# audio3.net
KiCad netlist of a schematic drawn in EAGLE
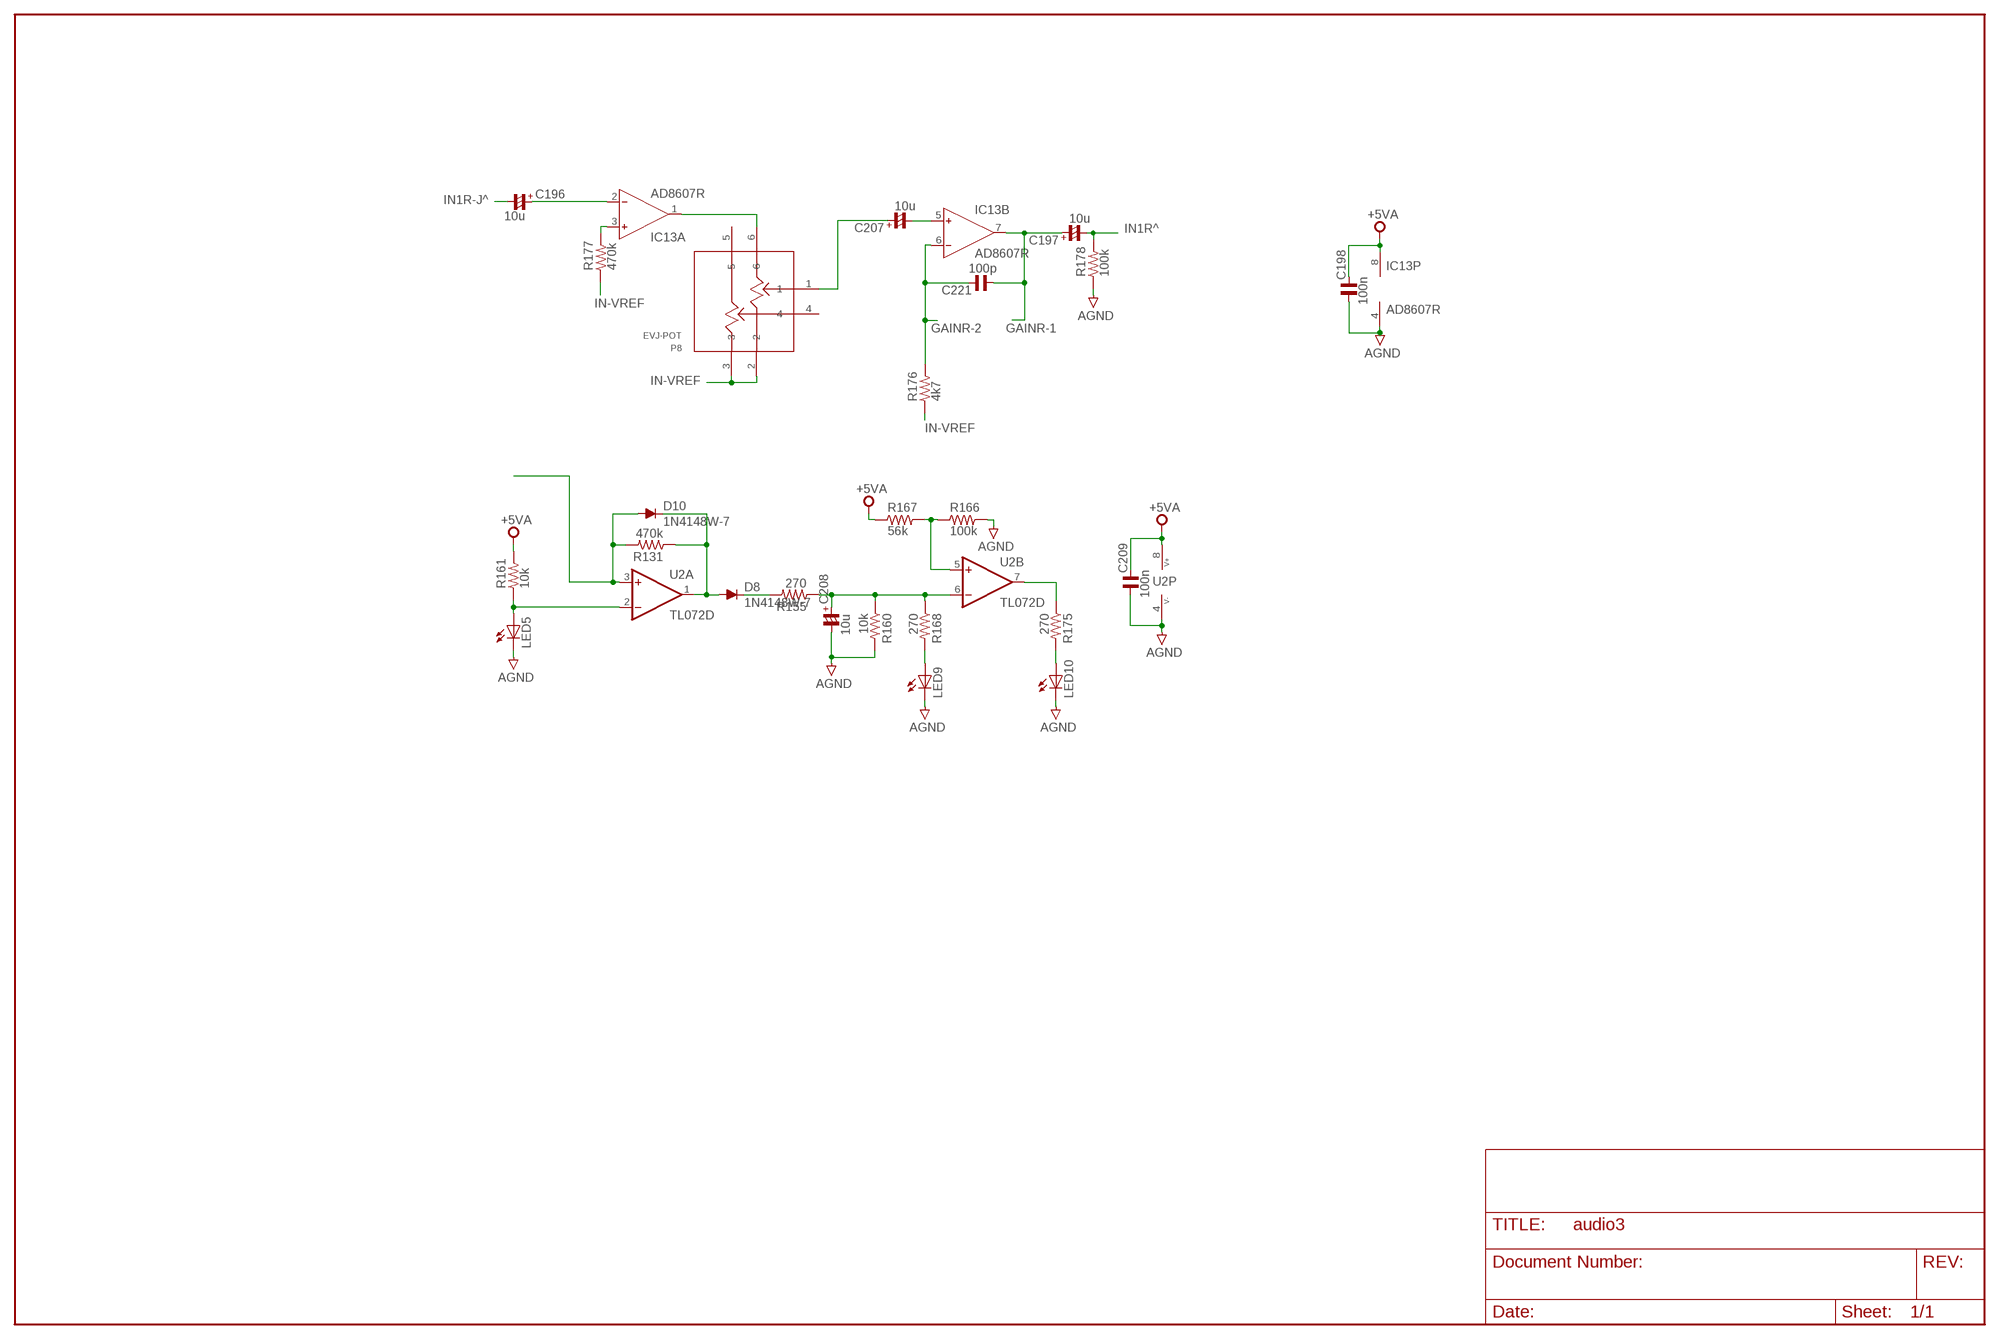
[diagram p0: schematic, sheet 1]

(export (version "E")
  (design (tool "Eeschema 10.0.6"))
  (components
    (comp (ref "C196")
      (value "10u")
      (footprint "eagle-import:C1206_T")
      (libsource (lib "eagle-import") (part "CP_1206/T"))
    )
    (comp (ref "C197")
      (value "10u")
      (footprint "eagle-import:C1206_T")
      (libsource (lib "eagle-import") (part "CP_1206/T"))
    )
    (comp (ref "C198")
      (value "100n")
      (footprint "eagle-import:C0603")
      (libsource (lib "eagle-import") (part "C_0603"))
    )
    (comp (ref "C207")
      (value "10u")
      (footprint "eagle-import:C1206_T")
      (libsource (lib "eagle-import") (part "CP_1206/T"))
    )
    (comp (ref "C208")
      (value "10u")
      (footprint "eagle-import:C1206_T")
      (libsource (lib "eagle-import") (part "CP_1206/T"))
    )
    (comp (ref "C209")
      (value "100n")
      (footprint "eagle-import:C0603")
      (libsource (lib "eagle-import") (part "C_0603"))
    )
    (comp (ref "C221")
      (value "100p")
      (footprint "eagle-import:C0603")
      (libsource (lib "eagle-import") (part "C_0603"))
    )
    (comp (ref "D8")
      (value "1N4148W-7")
      (footprint "eagle-import:SOD123")
      (libsource (lib "eagle-import") (part "1N4148W-7"))
    )
    (comp (ref "D10")
      (value "1N4148W-7")
      (footprint "eagle-import:SOD123")
      (libsource (lib "eagle-import") (part "1N4148W-7"))
    )
    (comp (ref "IC13")
      (value "AD8607R")
      (footprint "eagle-import:SO8")
      (fields (field (name "MPN") "AD8607ARMZ-R2"))
      (libsource (lib "eagle-import") (part "AD8607R"))
    )
    (comp (ref "LED5")
      (value "LEDCHIPLED_0805")
      (footprint "eagle-import:CHIPLED_0805")
      (libsource (lib "eagle-import") (part "LEDCHIPLED_0805"))
    )
    (comp (ref "LED9")
      (value "LEDCHIPLED_0805")
      (footprint "eagle-import:CHIPLED_0805")
      (libsource (lib "eagle-import") (part "LEDCHIPLED_0805"))
    )
    (comp (ref "LED10")
      (value "LEDCHIPLED_0805")
      (footprint "eagle-import:CHIPLED_0805")
      (libsource (lib "eagle-import") (part "LEDCHIPLED_0805"))
    )
    (comp (ref "P8")
      (value "EVJ-POT")
      (footprint "eagle-import:EVJ-POT")
      (libsource (lib "eagle-import") (part "EVJ-POT"))
    )
    (comp (ref "R131")
      (value "470k")
      (footprint "eagle-import:R0603")
      (libsource (lib "eagle-import") (part "R_0603"))
    )
    (comp (ref "R155")
      (value "270")
      (footprint "eagle-import:R0603")
      (libsource (lib "eagle-import") (part "R_0603"))
    )
    (comp (ref "R160")
      (value "10k")
      (footprint "eagle-import:R0603")
      (libsource (lib "eagle-import") (part "R_0603"))
    )
    (comp (ref "R161")
      (value "10k")
      (footprint "eagle-import:R0603")
      (libsource (lib "eagle-import") (part "R_0603"))
    )
    (comp (ref "R166")
      (value "100k")
      (footprint "eagle-import:R0603")
      (libsource (lib "eagle-import") (part "R_0603"))
    )
    (comp (ref "R167")
      (value "56k")
      (footprint "eagle-import:R0603")
      (libsource (lib "eagle-import") (part "R_0603"))
    )
    (comp (ref "R168")
      (value "270")
      (footprint "eagle-import:R0603")
      (libsource (lib "eagle-import") (part "R_0603"))
    )
    (comp (ref "R175")
      (value "270")
      (footprint "eagle-import:R0603")
      (libsource (lib "eagle-import") (part "R_0603"))
    )
    (comp (ref "R176")
      (value "4k7")
      (footprint "eagle-import:R0603")
      (libsource (lib "eagle-import") (part "R_0603"))
    )
    (comp (ref "R177")
      (value "470k")
      (footprint "eagle-import:R0603")
      (libsource (lib "eagle-import") (part "R_0603"))
    )
    (comp (ref "R178")
      (value "100k")
      (footprint "eagle-import:R0603")
      (libsource (lib "eagle-import") (part "R_0603"))
    )
    (comp (ref "U2")
      (value "TL072D")
      (footprint "eagle-import:SO08")
      (libsource (lib "eagle-import") (part "TL072D"))
    )
  )
  (nets
    (net (code "1") (name "+5VA") (class "Default")
      (node (ref "C198") (pin "2") (pinfunction "2_2") (pintype "passive"))
      (node (ref "C209") (pin "2") (pinfunction "2_2") (pintype "passive"))
      (node (ref "IC13") (pin "8") (pinfunction "V+_8") (pintype "power_in"))
      (node (ref "R161") (pin "2") (pinfunction "2_2") (pintype "passive"))
      (node (ref "R167") (pin "1") (pinfunction "1_1") (pintype "passive"))
      (node (ref "U2") (pin "8") (pinfunction "V+_8") (pintype "power_in"))
    )
    (net (code "2") (name "/GAINR-1") (class "Default")
      (node (ref "C197") (pin "+") (pinfunction "+_+") (pintype "passive"))
      (node (ref "C221") (pin "1") (pinfunction "1_1") (pintype "passive"))
      (node (ref "IC13") (pin "7") (pinfunction "OUT_7") (pintype "output"))
    )
    (net (code "3") (name "/GAINR-2") (class "Default")
      (node (ref "C221") (pin "2") (pinfunction "2_2") (pintype "passive"))
      (node (ref "IC13") (pin "6") (pinfunction "IN-_6") (pintype "input"))
      (node (ref "R176") (pin "2") (pinfunction "2_2") (pintype "passive"))
    )
    (net (code "4") (name "/IN-VREF") (class "Default")
      (node (ref "P8") (pin "2") (pinfunction "2_2") (pintype "bidirectional"))
      (node (ref "P8") (pin "3") (pinfunction "3_3") (pintype "bidirectional"))
      (node (ref "R176") (pin "1") (pinfunction "1_1") (pintype "passive"))
      (node (ref "R177") (pin "1") (pinfunction "1_1") (pintype "passive"))
    )
    (net (code "5") (name "/IN1R-J^") (class "Default")
      (node (ref "C196") (pin "-") (pinfunction "-_-") (pintype "passive"))
    )
    (net (code "6") (name "/IN1R^") (class "Default")
      (node (ref "C197") (pin "-") (pinfunction "-_-") (pintype "passive"))
      (node (ref "R178") (pin "2") (pinfunction "2_2") (pintype "passive"))
    )
    (net (code "7") (name "AGND") (class "Default")
      (node (ref "C198") (pin "1") (pinfunction "1_1") (pintype "passive"))
      (node (ref "C208") (pin "-") (pinfunction "-_-") (pintype "passive"))
      (node (ref "C209") (pin "1") (pinfunction "1_1") (pintype "passive"))
      (node (ref "IC13") (pin "4") (pinfunction "V-_4") (pintype "power_in"))
      (node (ref "LED10") (pin "C") (pinfunction "C_C") (pintype "passive"))
      (node (ref "LED5") (pin "C") (pinfunction "C_C") (pintype "passive"))
      (node (ref "LED9") (pin "C") (pinfunction "C_C") (pintype "passive"))
      (node (ref "R160") (pin "2") (pinfunction "2_2") (pintype "passive"))
      (node (ref "R166") (pin "2") (pinfunction "2_2") (pintype "passive"))
      (node (ref "R178") (pin "1") (pinfunction "1_1") (pintype "passive"))
      (node (ref "U2") (pin "4") (pinfunction "V-_4") (pintype "power_in"))
    )
    (net (code "8") (name "Net-(C207-Pad+)") (class "Default")
      (node (ref "C207") (pin "+") (pinfunction "+_+") (pintype "passive"))
      (node (ref "P8") (pin "1") (pinfunction "1_1") (pintype "bidirectional"))
    )
    (net (code "9") (name "Net-(D8-PadC)") (class "Default")
      (node (ref "D8") (pin "C") (pinfunction "C_C") (pintype "passive"))
      (node (ref "R155") (pin "2") (pinfunction "2_2") (pintype "passive"))
    )
    (net (code "10") (name "Net-(IC13A-IN+)") (class "Default")
      (node (ref "IC13") (pin "3") (pinfunction "IN+_3") (pintype "input"))
      (node (ref "R177") (pin "2") (pinfunction "2_2") (pintype "passive"))
    )
    (net (code "11") (name "Net-(IC13A-IN-)") (class "Default")
      (node (ref "C196") (pin "+") (pinfunction "+_+") (pintype "passive"))
      (node (ref "IC13") (pin "2") (pinfunction "IN-_2") (pintype "input"))
    )
    (net (code "12") (name "Net-(IC13A-OUT)") (class "Default")
      (node (ref "IC13") (pin "1") (pinfunction "OUT_1") (pintype "output"))
      (node (ref "P8") (pin "6") (pinfunction "6_6") (pintype "bidirectional"))
    )
    (net (code "13") (name "Net-(IC13B-IN+)") (class "Default")
      (node (ref "C207") (pin "-") (pinfunction "-_-") (pintype "passive"))
      (node (ref "IC13") (pin "5") (pinfunction "IN+_5") (pintype "input"))
    )
    (net (code "14") (name "Net-(LED9-PadA)") (class "Default")
      (node (ref "LED9") (pin "A") (pinfunction "A_A") (pintype "passive"))
      (node (ref "R168") (pin "2") (pinfunction "2_2") (pintype "passive"))
    )
    (net (code "15") (name "Net-(LED10-PadA)") (class "Default")
      (node (ref "LED10") (pin "A") (pinfunction "A_A") (pintype "passive"))
      (node (ref "R175") (pin "2") (pinfunction "2_2") (pintype "passive"))
    )
    (net (code "16") (name "Net-(U2A-+IN)") (class "Default")
      (node (ref "D10") (pin "A") (pinfunction "A_A") (pintype "passive"))
      (node (ref "R131") (pin "2") (pinfunction "2_2") (pintype "passive"))
      (node (ref "U2") (pin "3") (pinfunction "+IN_3") (pintype "input"))
    )
    (net (code "17") (name "Net-(U2A--IN)") (class "Default")
      (node (ref "LED5") (pin "A") (pinfunction "A_A") (pintype "passive"))
      (node (ref "R161") (pin "1") (pinfunction "1_1") (pintype "passive"))
      (node (ref "U2") (pin "2") (pinfunction "-IN_2") (pintype "input"))
    )
    (net (code "18") (name "Net-(U2A-OUT)") (class "Default")
      (node (ref "D10") (pin "C") (pinfunction "C_C") (pintype "passive"))
      (node (ref "D8") (pin "A") (pinfunction "A_A") (pintype "passive"))
      (node (ref "R131") (pin "1") (pinfunction "1_1") (pintype "passive"))
      (node (ref "U2") (pin "1") (pinfunction "OUT_1") (pintype "output"))
    )
    (net (code "19") (name "Net-(U2B-+IN)") (class "Default")
      (node (ref "R166") (pin "1") (pinfunction "1_1") (pintype "passive"))
      (node (ref "R167") (pin "2") (pinfunction "2_2") (pintype "passive"))
      (node (ref "U2") (pin "5") (pinfunction "+IN_5") (pintype "input"))
    )
    (net (code "20") (name "Net-(U2B--IN)") (class "Default")
      (node (ref "C208") (pin "+") (pinfunction "+_+") (pintype "passive"))
      (node (ref "R155") (pin "1") (pinfunction "1_1") (pintype "passive"))
      (node (ref "R160") (pin "1") (pinfunction "1_1") (pintype "passive"))
      (node (ref "R168") (pin "1") (pinfunction "1_1") (pintype "passive"))
      (node (ref "U2") (pin "6") (pinfunction "-IN_6") (pintype "input"))
    )
    (net (code "21") (name "Net-(U2B-OUT)") (class "Default")
      (node (ref "R175") (pin "1") (pinfunction "1_1") (pintype "passive"))
      (node (ref "U2") (pin "7") (pinfunction "OUT_7") (pintype "output"))
    )
    (net (code "22") (name "unconnected-(P8-Pad4)") (class "Default")
      (node (ref "P8") (pin "4") (pinfunction "4_4") (pintype "bidirectional"))
    )
    (net (code "23") (name "unconnected-(P8-Pad5)") (class "Default")
      (node (ref "P8") (pin "5") (pinfunction "5_5") (pintype "bidirectional"))
    )
  )
)
